# MCU.net
KiCad netlist of a schematic drawn in Altium Designer
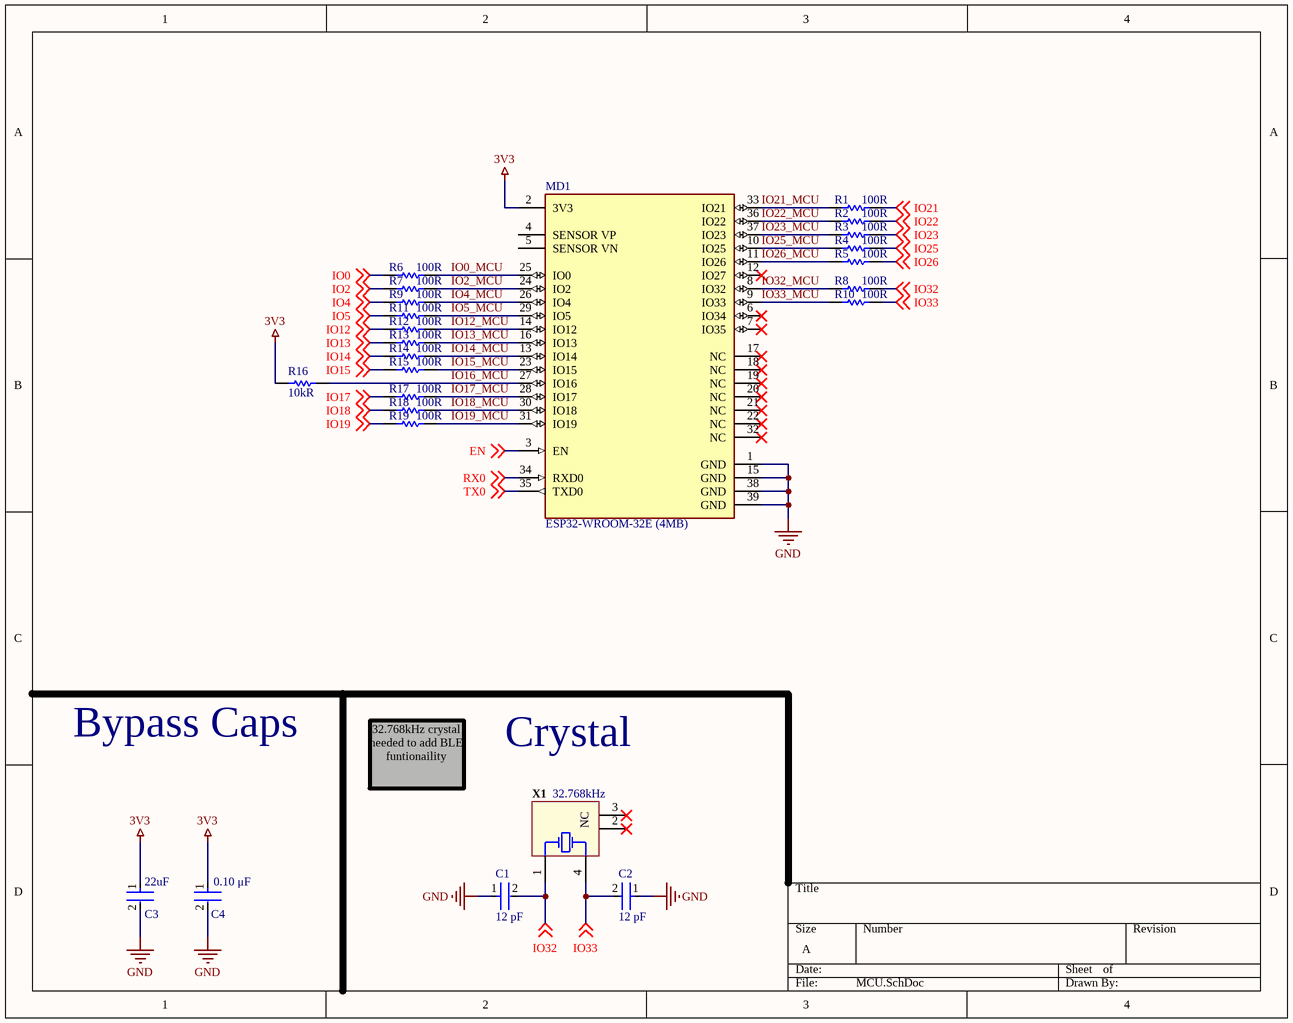
[diagram p0: MCU.SchDoc]

(export (version "E")
  (design (tool "Eeschema 10.0.6"))
  (components
    (comp (ref "C1")
      (value "12 pF")
      (footprint "FP-C0805C-DN-MFG")
      (description "CAP CER 12PF 50V C0G/NP0 0805")
      (fields (field (name "MANUFACTURER") "KEMET") (field (name "TOLERANCE") "0.05"))
      (libsource (lib "Altium Content Vault") (part "b4654b650e69147ec39a6b967a45e02"))
    )
    (comp (ref "C2")
      (value "12 pF")
      (footprint "FP-C0805C-DN-MFG")
      (description "CAP CER 12PF 50V C0G/NP0 0805")
      (fields (field (name "MANUFACTURER") "KEMET") (field (name "TOLERANCE") "0.05"))
      (libsource (lib "Altium Content Vault") (part "b4654b650e69147ec39a6b967a45e02"))
    )
    (comp (ref "C3")
      (value "GRM21BR60J226ME39L")
      (footprint "FP-GRM21B-0_15-MFG")
      (description "Chip Multilayer Ceramic Capacitors for General Purpose, 0805, 22uF, X5R, 15%, 20%, 6.3V")
      (fields
        (field (name "VOLTAGE") "6.3V")
        (field (name "TOLERANCE") "20%")
        (field (name "CAPACITANCE") "22uF")
      )
      (libsource (lib "Altium Content Vault") (part "b4654b650e69147ec39a6b967a45e02"))
    )
    (comp (ref "C4")
      (value "0.10 μF")
      (footprint "FP-C1206C-EB-MFG")
      (description "CAP CER 0.1UF 100V X7R 1206")
      (fields
        (field (name "TOLERANCE") "0.1")
        (field (name "OCTOPART") "https://octopart.com/c1206c104k1ractu-kemet-89521")
      )
      (libsource (lib "Altium Content Vault") (part "b4654b650e69147ec39a6b967a45e02"))
    )
    (comp (ref "MD1")
      (value "ESP32-WROOM-32E (4MB)")
      (footprint "FP-ESP32-WROOM-32E_4MB-MFG")
      (description "RX TXRX MOD WIFI TRACE ANT SMD")
      (libsource (lib "Altium Content Vault") (part "7f842c3463a9561e2f6f9fdcd687e0f"))
    )
    (comp (ref "R1")
      (value "100R")
      (footprint "RESC3216X65X50NL15T25")
      (fields
        (field (name "MANUFACTURER") "Vishay Dale")
        (field (name "PART NUMBER") "TNPW1206100RBEEN")
        (field (name "TOLERANCE") "0.1%")
      )
      (libsource (lib "Altium Content Vault") (part "RES"))
    )
    (comp (ref "R2")
      (value "100R")
      (footprint "RESC3216X65X50NL15T25")
      (fields
        (field (name "MANUFACTURER") "Vishay Dale")
        (field (name "PART NUMBER") "TNPW1206100RBEEN")
        (field (name "TOLERANCE") "0.1%")
      )
      (libsource (lib "Altium Content Vault") (part "RES"))
    )
    (comp (ref "R3")
      (value "100R")
      (footprint "RESC3216X65X50NL15T25")
      (fields
        (field (name "MANUFACTURER") "Vishay Dale")
        (field (name "PART NUMBER") "TNPW1206100RBEEN")
        (field (name "TOLERANCE") "0.1%")
      )
      (libsource (lib "Altium Content Vault") (part "RES"))
    )
    (comp (ref "R4")
      (value "100R")
      (footprint "RESC3216X65X50NL15T25")
      (fields
        (field (name "MANUFACTURER") "Vishay Dale")
        (field (name "PART NUMBER") "TNPW1206100RBEEN")
        (field (name "TOLERANCE") "0.1%")
      )
      (libsource (lib "Altium Content Vault") (part "RES"))
    )
    (comp (ref "R5")
      (value "100R")
      (footprint "RESC3216X65X50NL15T25")
      (fields
        (field (name "MANUFACTURER") "Vishay Dale")
        (field (name "PART NUMBER") "TNPW1206100RBEEN")
        (field (name "TOLERANCE") "0.1%")
      )
      (libsource (lib "Altium Content Vault") (part "RES"))
    )
    (comp (ref "R6")
      (value "100R")
      (footprint "RESC3216X65X50NL15T25")
      (fields
        (field (name "MANUFACTURER") "Vishay Dale")
        (field (name "PART NUMBER") "TNPW1206100RBEEN")
        (field (name "TOLERANCE") "0.1%")
      )
      (libsource (lib "Altium Content Vault") (part "RES"))
    )
    (comp (ref "R7")
      (value "100R")
      (footprint "RESC3216X65X50NL15T25")
      (fields
        (field (name "MANUFACTURER") "Vishay Dale")
        (field (name "PART NUMBER") "TNPW1206100RBEEN")
        (field (name "TOLERANCE") "0.1%")
      )
      (libsource (lib "Altium Content Vault") (part "RES"))
    )
    (comp (ref "R8")
      (value "100R")
      (footprint "RESC3216X65X50NL15T25")
      (fields
        (field (name "MANUFACTURER") "Vishay Dale")
        (field (name "PART NUMBER") "TNPW1206100RBEEN")
        (field (name "TOLERANCE") "0.1%")
      )
      (libsource (lib "Altium Content Vault") (part "RES"))
    )
    (comp (ref "R9")
      (value "100R")
      (footprint "RESC3216X65X50NL15T25")
      (fields
        (field (name "MANUFACTURER") "Vishay Dale")
        (field (name "PART NUMBER") "TNPW1206100RBEEN")
        (field (name "TOLERANCE") "0.1%")
      )
      (libsource (lib "Altium Content Vault") (part "RES"))
    )
    (comp (ref "R10")
      (value "100R")
      (footprint "RESC3216X65X50NL15T25")
      (fields
        (field (name "MANUFACTURER") "Vishay Dale")
        (field (name "PART NUMBER") "TNPW1206100RBEEN")
        (field (name "TOLERANCE") "0.1%")
      )
      (libsource (lib "Altium Content Vault") (part "RES"))
    )
    (comp (ref "R11")
      (value "100R")
      (footprint "RESC3216X65X50NL15T25")
      (fields
        (field (name "MANUFACTURER") "Vishay Dale")
        (field (name "PART NUMBER") "TNPW1206100RBEEN")
        (field (name "TOLERANCE") "0.1%")
      )
      (libsource (lib "Altium Content Vault") (part "RES"))
    )
    (comp (ref "R12")
      (value "100R")
      (footprint "RESC3216X65X50NL15T25")
      (fields
        (field (name "MANUFACTURER") "Vishay Dale")
        (field (name "PART NUMBER") "TNPW1206100RBEEN")
        (field (name "TOLERANCE") "0.1%")
      )
      (libsource (lib "Altium Content Vault") (part "RES"))
    )
    (comp (ref "R13")
      (value "100R")
      (footprint "RESC3216X65X50NL15T25")
      (fields
        (field (name "MANUFACTURER") "Vishay Dale")
        (field (name "PART NUMBER") "TNPW1206100RBEEN")
        (field (name "TOLERANCE") "0.1%")
      )
      (libsource (lib "Altium Content Vault") (part "RES"))
    )
    (comp (ref "R14")
      (value "100R")
      (footprint "RESC3216X65X50NL15T25")
      (fields
        (field (name "MANUFACTURER") "Vishay Dale")
        (field (name "PART NUMBER") "TNPW1206100RBEEN")
        (field (name "TOLERANCE") "0.1%")
      )
      (libsource (lib "Altium Content Vault") (part "RES"))
    )
    (comp (ref "R15")
      (value "100R")
      (footprint "RESC3216X65X50NL15T25")
      (fields
        (field (name "MANUFACTURER") "Vishay Dale")
        (field (name "PART NUMBER") "TNPW1206100RBEEN")
        (field (name "TOLERANCE") "0.1%")
      )
      (libsource (lib "Altium Content Vault") (part "RES"))
    )
    (comp (ref "R16")
      (value "10kR")
      (footprint "RESC2013X60X35NL10T20")
      (description "Chip Resistor, 10 KOhm, +/- 1%, 0.125 W, -55 to 155 degC, 0805 (2012 Metric), RoHS, Tape and Reel")
      (fields
        (field (name "MANUFACTURER") "Yageo")
        (field (name "MANUFACTURER PART NUMBER") "RC0805FR-0710KL")
      )
      (libsource (lib "Altium Content Vault") (part "RES-2"))
    )
    (comp (ref "R17")
      (value "100R")
      (footprint "RESC3216X65X50NL15T25")
      (fields
        (field (name "MANUFACTURER") "Vishay Dale")
        (field (name "PART NUMBER") "TNPW1206100RBEEN")
        (field (name "TOLERANCE") "0.1%")
      )
      (libsource (lib "Altium Content Vault") (part "RES"))
    )
    (comp (ref "R18")
      (value "100R")
      (footprint "RESC3216X65X50NL15T25")
      (fields
        (field (name "MANUFACTURER") "Vishay Dale")
        (field (name "PART NUMBER") "TNPW1206100RBEEN")
        (field (name "TOLERANCE") "0.1%")
      )
      (libsource (lib "Altium Content Vault") (part "RES"))
    )
    (comp (ref "R19")
      (value "100R")
      (footprint "RESC3216X65X50NL15T25")
      (fields
        (field (name "MANUFACTURER") "Vishay Dale")
        (field (name "PART NUMBER") "TNPW1206100RBEEN")
        (field (name "TOLERANCE") "0.1%")
      )
      (libsource (lib "Altium Content Vault") (part "RES"))
    )
    (comp (ref "X1")
      (value "ABS25-32.768KHZ-6-T")
      (footprint "ABRA-ABS25-4_V")
      (fields
        (field (name "FREQUENCY") "32.768kHz")
        (field (name "TOLERANCE") "20PPM")
        (field (name "MANUFACTURER") "Abracon")
      )
      (libsource (lib "Altium Content Vault") (part "ABRA-XTAL_1-4-4"))
    )
  )
  (nets
    (net (code "1") (name "/IO0_MCU") (class "Default")
      (node (ref "MD1") (pin "25") (pinfunction "IO0_25") (pintype "bidirectional"))
      (node (ref "R6") (pin "2") (pinfunction "2_2") (pintype "passive"))
    )
    (net (code "2") (name "/IO2_MCU") (class "Default")
      (node (ref "MD1") (pin "24") (pinfunction "IO2_24") (pintype "bidirectional"))
      (node (ref "R7") (pin "2") (pinfunction "2_2") (pintype "passive"))
    )
    (net (code "3") (name "/IO4_MCU") (class "Default")
      (node (ref "MD1") (pin "26") (pinfunction "IO4_26") (pintype "bidirectional"))
      (node (ref "R9") (pin "2") (pinfunction "2_2") (pintype "passive"))
    )
    (net (code "4") (name "/IO5_MCU") (class "Default")
      (node (ref "MD1") (pin "29") (pinfunction "IO5_29") (pintype "bidirectional"))
      (node (ref "R11") (pin "2") (pinfunction "2_2") (pintype "passive"))
    )
    (net (code "5") (name "/IO12_MCU") (class "Default")
      (node (ref "MD1") (pin "14") (pinfunction "IO12_14") (pintype "bidirectional"))
      (node (ref "R12") (pin "2") (pinfunction "2_2") (pintype "passive"))
    )
    (net (code "6") (name "/IO13_MCU") (class "Default")
      (node (ref "MD1") (pin "16") (pinfunction "IO13_16") (pintype "bidirectional"))
      (node (ref "R13") (pin "2") (pinfunction "2_2") (pintype "passive"))
    )
    (net (code "7") (name "/IO14_MCU") (class "Default")
      (node (ref "MD1") (pin "13") (pinfunction "IO14_13") (pintype "bidirectional"))
      (node (ref "R14") (pin "2") (pinfunction "2_2") (pintype "passive"))
    )
    (net (code "8") (name "/IO15_MCU") (class "Default")
      (node (ref "MD1") (pin "23") (pinfunction "IO15_23") (pintype "bidirectional"))
      (node (ref "R15") (pin "2") (pinfunction "2_2") (pintype "passive"))
    )
    (net (code "9") (name "/IO16_MCU") (class "Default")
      (node (ref "MD1") (pin "27") (pinfunction "IO16_27") (pintype "bidirectional"))
      (node (ref "R16") (pin "1") (pinfunction "1_1") (pintype "passive"))
    )
    (net (code "10") (name "/IO17_MCU") (class "Default")
      (node (ref "MD1") (pin "28") (pinfunction "IO17_28") (pintype "bidirectional"))
      (node (ref "R17") (pin "2") (pinfunction "2_2") (pintype "passive"))
    )
    (net (code "11") (name "/IO18_MCU") (class "Default")
      (node (ref "MD1") (pin "30") (pinfunction "IO18_30") (pintype "bidirectional"))
      (node (ref "R18") (pin "2") (pinfunction "2_2") (pintype "passive"))
    )
    (net (code "12") (name "/IO19_MCU") (class "Default")
      (node (ref "MD1") (pin "31") (pinfunction "IO19_31") (pintype "bidirectional"))
      (node (ref "R19") (pin "2") (pinfunction "2_2") (pintype "passive"))
    )
    (net (code "13") (name "/IO21_MCU") (class "Default")
      (node (ref "MD1") (pin "33") (pinfunction "IO21_33") (pintype "bidirectional"))
      (node (ref "R1") (pin "1") (pinfunction "1_1") (pintype "passive"))
    )
    (net (code "14") (name "/IO22_MCU") (class "Default")
      (node (ref "MD1") (pin "36") (pinfunction "IO22_36") (pintype "bidirectional"))
      (node (ref "R2") (pin "1") (pinfunction "1_1") (pintype "passive"))
    )
    (net (code "15") (name "/IO23_MCU") (class "Default")
      (node (ref "MD1") (pin "37") (pinfunction "IO23_37") (pintype "bidirectional"))
      (node (ref "R3") (pin "1") (pinfunction "1_1") (pintype "passive"))
    )
    (net (code "16") (name "/IO25_MCU") (class "Default")
      (node (ref "MD1") (pin "10") (pinfunction "IO25_10") (pintype "bidirectional"))
      (node (ref "R4") (pin "1") (pinfunction "1_1") (pintype "passive"))
    )
    (net (code "17") (name "/IO26_MCU") (class "Default")
      (node (ref "MD1") (pin "11") (pinfunction "IO26_11") (pintype "bidirectional"))
      (node (ref "R5") (pin "1") (pinfunction "1_1") (pintype "passive"))
    )
    (net (code "18") (name "/IO32_MCU") (class "Default")
      (node (ref "MD1") (pin "8") (pinfunction "IO32_8") (pintype "bidirectional"))
      (node (ref "R8") (pin "1") (pinfunction "1_1") (pintype "passive"))
    )
    (net (code "19") (name "/IO33_MCU") (class "Default")
      (node (ref "MD1") (pin "9") (pinfunction "IO33_9") (pintype "bidirectional"))
      (node (ref "R10") (pin "1") (pinfunction "1_1") (pintype "passive"))
    )
    (net (code "20") (name "3V3") (class "Default")
      (node (ref "C3") (pin "1") (pinfunction "1_1") (pintype "passive"))
      (node (ref "C4") (pin "1") (pinfunction "1_1") (pintype "passive"))
      (node (ref "MD1") (pin "2") (pinfunction "3V3_2") (pintype "power_in"))
      (node (ref "R16") (pin "2") (pinfunction "2_2") (pintype "passive"))
    )
    (net (code "21") (name "EN") (class "Default")
      (node (ref "MD1") (pin "3") (pinfunction "EN_3") (pintype "input"))
    )
    (net (code "22") (name "GND") (class "Default")
      (node (ref "C1") (pin "1") (pinfunction "1_1") (pintype "passive"))
      (node (ref "C2") (pin "1") (pinfunction "1_1") (pintype "passive"))
      (node (ref "C3") (pin "2") (pinfunction "2_2") (pintype "passive"))
      (node (ref "C4") (pin "2") (pinfunction "2_2") (pintype "passive"))
      (node (ref "MD1") (pin "1") (pinfunction "GND_1") (pintype "power_in"))
      (node (ref "MD1") (pin "15") (pinfunction "GND_15") (pintype "power_in"))
      (node (ref "MD1") (pin "38") (pinfunction "GND_38") (pintype "power_in"))
      (node (ref "MD1") (pin "39") (pinfunction "GND_39") (pintype "power_in"))
    )
    (net (code "23") (name "IO0") (class "Default")
      (node (ref "R6") (pin "1") (pinfunction "1_1") (pintype "passive"))
    )
    (net (code "24") (name "IO2") (class "Default")
      (node (ref "R7") (pin "1") (pinfunction "1_1") (pintype "passive"))
    )
    (net (code "25") (name "IO4") (class "Default")
      (node (ref "R9") (pin "1") (pinfunction "1_1") (pintype "passive"))
    )
    (net (code "26") (name "IO5") (class "Default")
      (node (ref "R11") (pin "1") (pinfunction "1_1") (pintype "passive"))
    )
    (net (code "27") (name "IO12") (class "Default")
      (node (ref "R12") (pin "1") (pinfunction "1_1") (pintype "passive"))
    )
    (net (code "28") (name "IO13") (class "Default")
      (node (ref "R13") (pin "1") (pinfunction "1_1") (pintype "passive"))
    )
    (net (code "29") (name "IO14") (class "Default")
      (node (ref "R14") (pin "1") (pinfunction "1_1") (pintype "passive"))
    )
    (net (code "30") (name "IO15") (class "Default")
      (node (ref "R15") (pin "1") (pinfunction "1_1") (pintype "passive"))
    )
    (net (code "31") (name "IO17") (class "Default")
      (node (ref "R17") (pin "1") (pinfunction "1_1") (pintype "passive"))
    )
    (net (code "32") (name "IO18") (class "Default")
      (node (ref "R18") (pin "1") (pinfunction "1_1") (pintype "passive"))
    )
    (net (code "33") (name "IO19") (class "Default")
      (node (ref "R19") (pin "1") (pinfunction "1_1") (pintype "passive"))
    )
    (net (code "34") (name "IO21") (class "Default")
      (node (ref "R1") (pin "2") (pinfunction "2_2") (pintype "passive"))
    )
    (net (code "35") (name "IO22") (class "Default")
      (node (ref "R2") (pin "2") (pinfunction "2_2") (pintype "passive"))
    )
    (net (code "36") (name "IO23") (class "Default")
      (node (ref "R3") (pin "2") (pinfunction "2_2") (pintype "passive"))
    )
    (net (code "37") (name "IO25") (class "Default")
      (node (ref "R4") (pin "2") (pinfunction "2_2") (pintype "passive"))
    )
    (net (code "38") (name "IO26") (class "Default")
      (node (ref "R5") (pin "2") (pinfunction "2_2") (pintype "passive"))
    )
    (net (code "39") (name "IO32") (class "Default")
      (node (ref "C1") (pin "2") (pinfunction "2_2") (pintype "passive"))
      (node (ref "R8") (pin "2") (pinfunction "2_2") (pintype "passive"))
      (node (ref "X1") (pin "1") (pinfunction "X1_1") (pintype "passive"))
    )
    (net (code "40") (name "IO33") (class "Default")
      (node (ref "C2") (pin "2") (pinfunction "2_2") (pintype "passive"))
      (node (ref "R10") (pin "2") (pinfunction "2_2") (pintype "passive"))
      (node (ref "X1") (pin "4") (pinfunction "X2_4") (pintype "passive"))
    )
    (net (code "41") (name "RX0") (class "Default")
      (node (ref "MD1") (pin "34") (pinfunction "RXD0_34") (pintype "input"))
    )
    (net (code "42") (name "TX0") (class "Default")
      (node (ref "MD1") (pin "35") (pinfunction "TXD0_35") (pintype "output"))
    )
    (net (code "43") (name "unconnected-(MD1-IO27-Pad12)") (class "Default")
      (node (ref "MD1") (pin "12") (pinfunction "IO27_12") (pintype "bidirectional+no_connect"))
    )
    (net (code "44") (name "unconnected-(MD1-IO34-Pad6)") (class "Default")
      (node (ref "MD1") (pin "6") (pinfunction "IO34_6") (pintype "bidirectional+no_connect"))
    )
    (net (code "45") (name "unconnected-(MD1-IO35-Pad7)") (class "Default")
      (node (ref "MD1") (pin "7") (pinfunction "IO35_7") (pintype "bidirectional+no_connect"))
    )
    (net (code "46") (name "unconnected-(MD1-NC-Pad17)") (class "Default")
      (node (ref "MD1") (pin "17") (pinfunction "NC_17") (pintype "passive+no_connect"))
    )
    (net (code "47") (name "unconnected-(MD1-NC-Pad18)") (class "Default")
      (node (ref "MD1") (pin "18") (pinfunction "NC_18") (pintype "passive+no_connect"))
    )
    (net (code "48") (name "unconnected-(MD1-NC-Pad19)") (class "Default")
      (node (ref "MD1") (pin "19") (pinfunction "NC_19") (pintype "passive+no_connect"))
    )
    (net (code "49") (name "unconnected-(MD1-NC-Pad20)") (class "Default")
      (node (ref "MD1") (pin "20") (pinfunction "NC_20") (pintype "passive+no_connect"))
    )
    (net (code "50") (name "unconnected-(MD1-NC-Pad21)") (class "Default")
      (node (ref "MD1") (pin "21") (pinfunction "NC_21") (pintype "passive+no_connect"))
    )
    (net (code "51") (name "unconnected-(MD1-NC-Pad22)") (class "Default")
      (node (ref "MD1") (pin "22") (pinfunction "NC_22") (pintype "passive+no_connect"))
    )
    (net (code "52") (name "unconnected-(MD1-NC-Pad32)") (class "Default")
      (node (ref "MD1") (pin "32") (pinfunction "NC_32") (pintype "passive+no_connect"))
    )
    (net (code "53") (name "unconnected-(MD1-SENSOR_VN-Pad5)") (class "Default")
      (node (ref "MD1") (pin "5") (pinfunction "SENSOR_VN_5") (pintype "passive"))
    )
    (net (code "54") (name "unconnected-(MD1-SENSOR_VP-Pad4)") (class "Default")
      (node (ref "MD1") (pin "4") (pinfunction "SENSOR_VP_4") (pintype "passive"))
    )
    (net (code "55") (name "unconnected-(X1-NC-Pad2)") (class "Default")
      (node (ref "X1") (pin "2") (pinfunction "NC_2") (pintype "passive+no_connect"))
    )
    (net (code "56") (name "unconnected-(X1-NC-Pad3)") (class "Default")
      (node (ref "X1") (pin "3") (pinfunction "NC_3") (pintype "passive+no_connect"))
    )
  )
)
